# NEO-M8N_BMP280_Wing.net
KiCad netlist of a schematic drawn in EAGLE
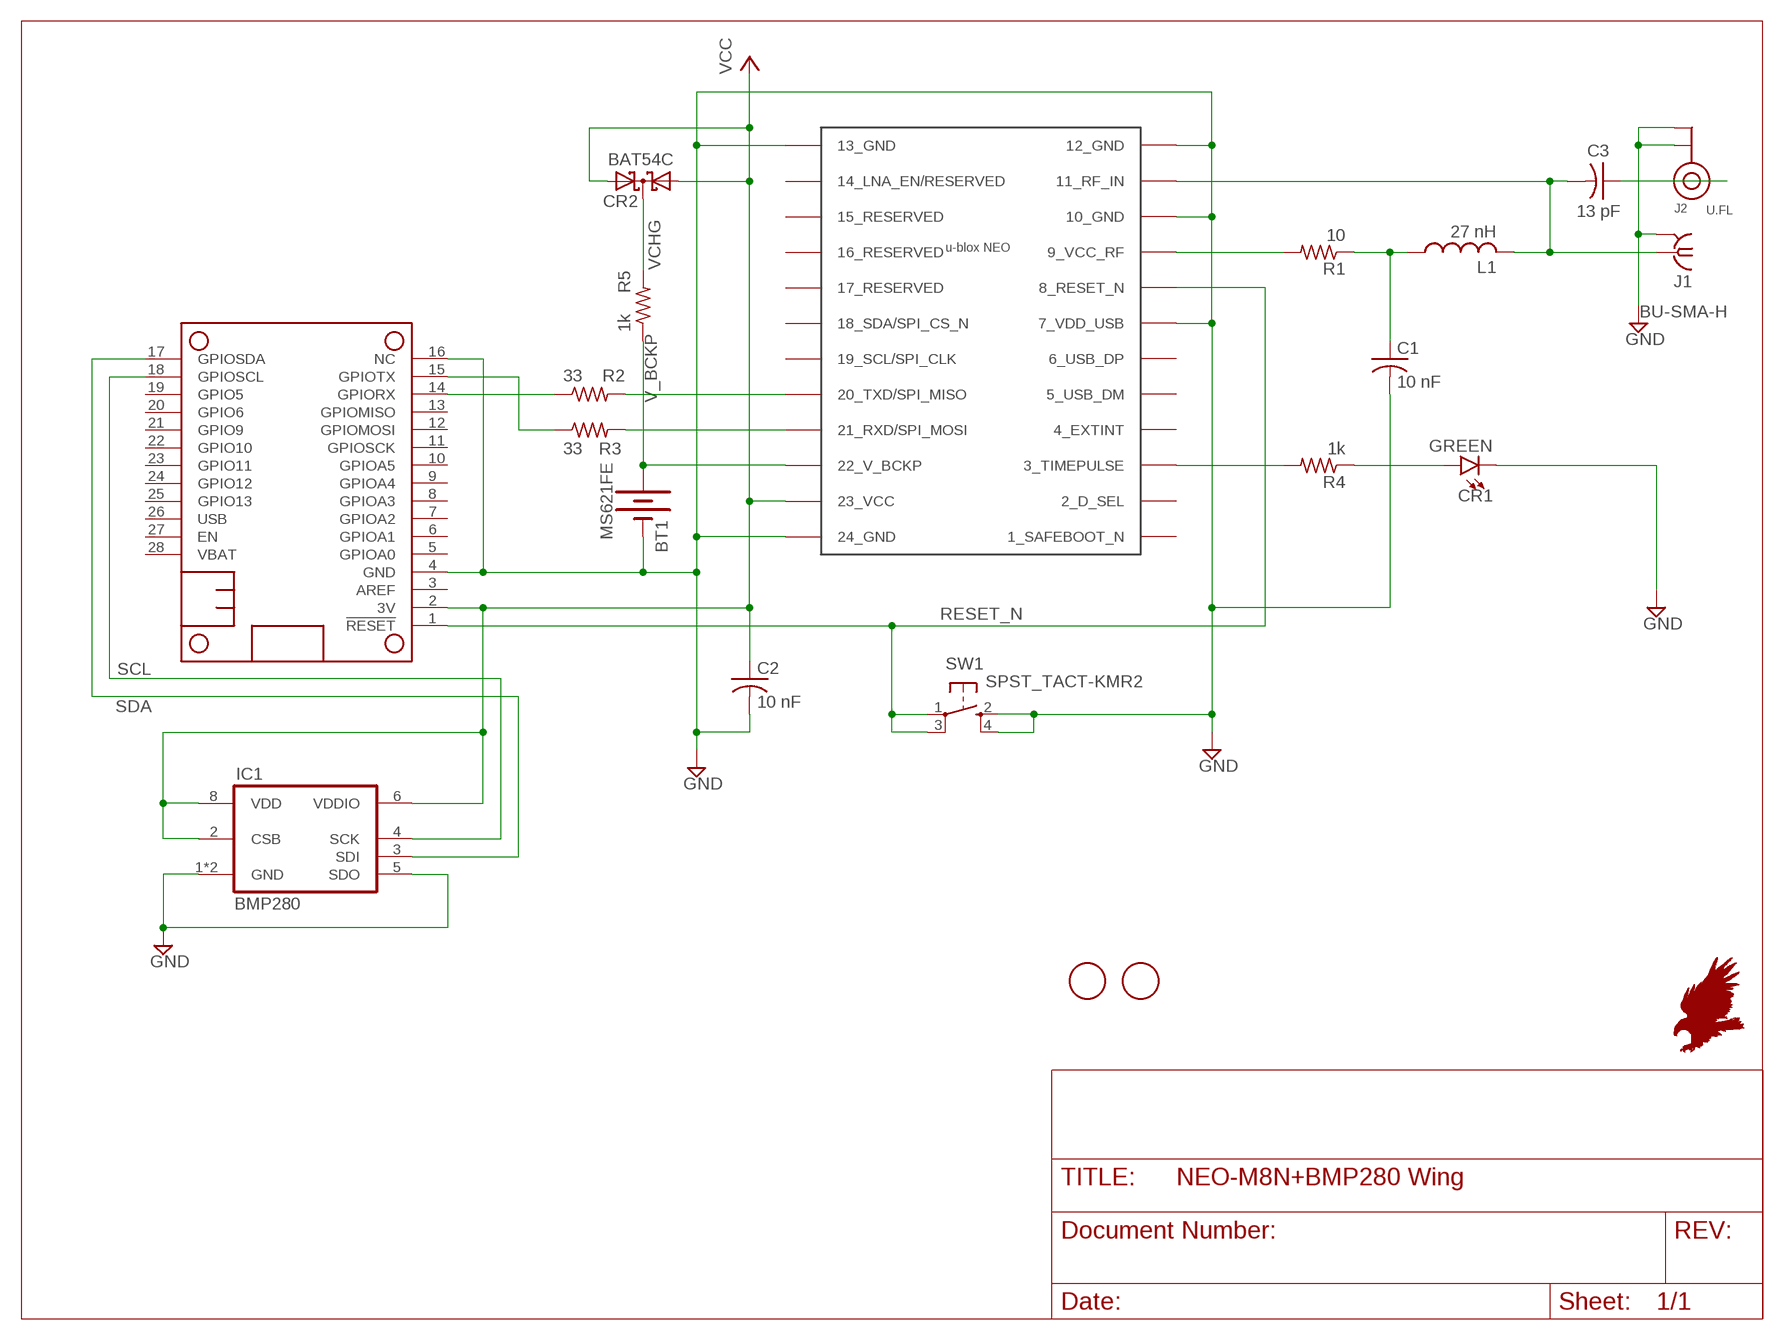
[diagram p0: schematic, sheet 1]

(export (version "E")
  (design (tool "Eeschema 10.0.6"))
  (components
    (comp (ref "BT1")
      (value "MS621FE")
      (footprint "eagle-import:BATTCON-6.8MM")
      (libsource (lib "eagle-import") (part "BATTERY-6.8MM_SMD"))
    )
    (comp (ref "C1")
      (value "10 nF")
      (footprint "eagle-import:C0402")
      (libsource (lib "eagle-import") (part "C-USC0402"))
    )
    (comp (ref "C2")
      (value "10 nF")
      (footprint "eagle-import:C0402")
      (libsource (lib "eagle-import") (part "C-USC0402"))
    )
    (comp (ref "C3")
      (value "13 pF")
      (footprint "eagle-import:C0402")
      (libsource (lib "eagle-import") (part "C-USC0402"))
    )
    (comp (ref "CR1")
      (value "GREEN")
      (footprint "eagle-import:LED-0603")
      (libsource (lib "eagle-import") (part "LED-GREEN0603"))
    )
    (comp (ref "CR2")
      (value "BAT54C")
      (footprint "eagle-import:SOT23")
      (libsource (lib "eagle-import") (part "BAT54C"))
    )
    (comp (ref "FID1")
      (value "FIDUCIAL")
      (footprint "eagle-import:FIDUCIAL_1MM")
      (libsource (lib "eagle-import") (part "FIDUCIAL"))
    )
    (comp (ref "FID2")
      (value "FIDUCIAL")
      (footprint "eagle-import:FIDUCIAL_1MM")
      (libsource (lib "eagle-import") (part "FIDUCIAL"))
    )
    (comp (ref "IC1")
      (value "BMP280")
      (footprint "eagle-import:BMP280")
      (libsource (lib "eagle-import") (part "BMP280"))
    )
    (comp (ref "J1")
      (value "BU-SMA-H")
      (footprint "eagle-import:BU-SMA-H")
      (libsource (lib "eagle-import") (part "BU-SMA-H"))
    )
    (comp (ref "J2")
      (value "U.FL")
      (footprint "eagle-import:U.FL")
      (libsource (lib "eagle-import") (part "ANTENNA_U.FL"))
    )
    (comp (ref "L1")
      (value "27 nH")
      (footprint "eagle-import:L0402")
      (libsource (lib "eagle-import") (part "L-US0402"))
    )
    (comp (ref "MS1")
      (value "FEATHERWING")
      (footprint "eagle-import:FEATHERWING")
      (libsource (lib "eagle-import") (part "FEATHERWING"))
    )
    (comp (ref "R1")
      (value "10")
      (footprint "eagle-import:R0805")
      (libsource (lib "eagle-import") (part "R-US_R0805"))
    )
    (comp (ref "R2")
      (value "33")
      (footprint "eagle-import:R0805")
      (libsource (lib "eagle-import") (part "R-US_R0805"))
    )
    (comp (ref "R3")
      (value "33")
      (footprint "eagle-import:R0805")
      (libsource (lib "eagle-import") (part "R-US_R0805"))
    )
    (comp (ref "R4")
      (value "1k")
      (footprint "eagle-import:R0805")
      (libsource (lib "eagle-import") (part "R-US_R0805"))
    )
    (comp (ref "R5")
      (value "1k")
      (footprint "eagle-import:R0805")
      (libsource (lib "eagle-import") (part "R-US_R0805"))
    )
    (comp (ref "SW1")
      (value "SPST_TACT-KMR2")
      (footprint "eagle-import:KMR2")
      (libsource (lib "eagle-import") (part "SPST_TACT-KMR2"))
    )
    (comp (ref "U$2")
      (value "NEO-M8")
      (footprint "eagle-import:NEO-M8")
      (libsource (lib "eagle-import") (part "NEO-M8"))
    )
  )
  (nets
    (net (code "1") (name "/RESET_N") (class "Default")
      (node (ref "MS1") (pin "1") (pinfunction "~{RESET}_1") (pintype "input"))
      (node (ref "SW1") (pin "1") (pinfunction "P_1") (pintype "passive"))
      (node (ref "SW1") (pin "3") (pinfunction "P1_3") (pintype "passive"))
      (node (ref "U$2") (pin "8") (pinfunction "8_RESET_N_8") (pintype "bidirectional"))
    )
    (net (code "2") (name "/SCL") (class "Default")
      (node (ref "IC1") (pin "4") (pinfunction "SCK_4") (pintype "bidirectional"))
      (node (ref "MS1") (pin "18") (pinfunction "GPIOSCL_18") (pintype "bidirectional"))
    )
    (net (code "3") (name "/SDA") (class "Default")
      (node (ref "IC1") (pin "3") (pinfunction "SDI_3") (pintype "bidirectional"))
      (node (ref "MS1") (pin "17") (pinfunction "GPIOSDA_17") (pintype "bidirectional"))
    )
    (net (code "4") (name "/USB") (class "Default")
      (node (ref "MS1") (pin "26") (pinfunction "USB_26") (pintype "power_in"))
    )
    (net (code "5") (name "/VBAT") (class "Default")
      (node (ref "MS1") (pin "28") (pinfunction "VBAT_28") (pintype "power_in"))
    )
    (net (code "6") (name "/VCHG") (class "Default")
      (node (ref "CR2") (pin "3") (pinfunction "CC_3") (pintype "passive"))
      (node (ref "R5") (pin "2") (pinfunction "2_2") (pintype "passive"))
    )
    (net (code "7") (name "/V_BCKP") (class "Default")
      (node (ref "BT1") (pin "+") (pinfunction "+_+") (pintype "power_in"))
      (node (ref "R5") (pin "1") (pinfunction "1_1") (pintype "passive"))
      (node (ref "U$2") (pin "22") (pinfunction "22_V_BCKP_22") (pintype "bidirectional"))
    )
    (net (code "8") (name "GND") (class "Default")
      (node (ref "BT1") (pin "-") (pinfunction "-_-") (pintype "power_in"))
      (node (ref "C1") (pin "2") (pinfunction "2_2") (pintype "passive"))
      (node (ref "C2") (pin "2") (pinfunction "2_2") (pintype "passive"))
      (node (ref "CR1") (pin "C") (pinfunction "C_C") (pintype "passive"))
      (node (ref "IC1") (pin "1") (pinfunction "GND_1") (pintype "power_in"))
      (node (ref "IC1") (pin "5") (pinfunction "SDO_5") (pintype "input"))
      (node (ref "IC1") (pin "7") (pinfunction "GND_7") (pintype "power_in"))
      (node (ref "J1") (pin "2") (pinfunction "2_2") (pintype "passive"))
      (node (ref "J1") (pin "3") (pinfunction "2_3") (pintype "passive"))
      (node (ref "J1") (pin "4") (pinfunction "2_4") (pintype "passive"))
      (node (ref "J1") (pin "5") (pinfunction "2_5") (pintype "passive"))
      (node (ref "J2") (pin "1") (pinfunction "GND_1") (pintype "passive"))
      (node (ref "J2") (pin "2") (pinfunction "GND_2") (pintype "passive"))
      (node (ref "MS1") (pin "16") (pinfunction "NC_16") (pintype "passive"))
      (node (ref "MS1") (pin "4") (pinfunction "GND_4") (pintype "power_in"))
      (node (ref "SW1") (pin "2") (pinfunction "S_2") (pintype "passive"))
      (node (ref "SW1") (pin "4") (pinfunction "S1_4") (pintype "passive"))
      (node (ref "U$2") (pin "10") (pinfunction "10_GND_10") (pintype "bidirectional"))
      (node (ref "U$2") (pin "12") (pinfunction "12_GND_12") (pintype "bidirectional"))
      (node (ref "U$2") (pin "13") (pinfunction "13_GND_13") (pintype "bidirectional"))
      (node (ref "U$2") (pin "24") (pinfunction "24_GND_24") (pintype "bidirectional"))
      (node (ref "U$2") (pin "7") (pinfunction "7_VDD_USB_7") (pintype "bidirectional"))
    )
    (net (code "9") (name "Net-(CR1-PadA)") (class "Default")
      (node (ref "CR1") (pin "A") (pinfunction "A_A") (pintype "passive"))
      (node (ref "R4") (pin "1") (pinfunction "1_1") (pintype "passive"))
    )
    (net (code "10") (name "Net-(J2-SIGNAL)") (class "Default")
      (node (ref "C3") (pin "1") (pinfunction "1_1") (pintype "passive"))
      (node (ref "J2") (pin "3") (pinfunction "SIGNAL_3") (pintype "passive"))
    )
    (net (code "11") (name "Net-(L1-1)") (class "Default")
      (node (ref "C1") (pin "1") (pinfunction "1_1") (pintype "passive"))
      (node (ref "L1") (pin "P$1") (pinfunction "1_P$1") (pintype "passive"))
      (node (ref "R1") (pin "1") (pinfunction "1_1") (pintype "passive"))
    )
    (net (code "12") (name "Net-(L1-2)") (class "Default")
      (node (ref "C3") (pin "2") (pinfunction "2_2") (pintype "passive"))
      (node (ref "J1") (pin "1") (pinfunction "1_1") (pintype "passive"))
      (node (ref "L1") (pin "P$2") (pinfunction "2_P$2") (pintype "passive"))
      (node (ref "U$2") (pin "11") (pinfunction "11_RF_IN_11") (pintype "bidirectional"))
    )
    (net (code "13") (name "Net-(MS1-GPIORX)") (class "Default")
      (node (ref "MS1") (pin "14") (pinfunction "GPIORX_14") (pintype "bidirectional"))
      (node (ref "R2") (pin "1") (pinfunction "1_1") (pintype "passive"))
    )
    (net (code "14") (name "Net-(MS1-GPIOTX)") (class "Default")
      (node (ref "MS1") (pin "15") (pinfunction "GPIOTX_15") (pintype "bidirectional"))
      (node (ref "R3") (pin "1") (pinfunction "1_1") (pintype "passive"))
    )
    (net (code "15") (name "Net-(U$2-3_TIMEPULSE)") (class "Default")
      (node (ref "R4") (pin "2") (pinfunction "2_2") (pintype "passive"))
      (node (ref "U$2") (pin "3") (pinfunction "3_TIMEPULSE_3") (pintype "bidirectional"))
    )
    (net (code "16") (name "Net-(U$2-9_VCC_RF)") (class "Default")
      (node (ref "R1") (pin "2") (pinfunction "2_2") (pintype "passive"))
      (node (ref "U$2") (pin "9") (pinfunction "9_VCC_RF_9") (pintype "bidirectional"))
    )
    (net (code "17") (name "Net-(U$2-20_TXD{slash}SPI_MISO)") (class "Default")
      (node (ref "R2") (pin "2") (pinfunction "2_2") (pintype "passive"))
      (node (ref "U$2") (pin "20") (pinfunction "20_TXD/SPI_MISO_20") (pintype "bidirectional"))
    )
    (net (code "18") (name "Net-(U$2-21_RXD{slash}SPI_MOSI)") (class "Default")
      (node (ref "R3") (pin "2") (pinfunction "2_2") (pintype "passive"))
      (node (ref "U$2") (pin "21") (pinfunction "21_RXD/SPI_MOSI_21") (pintype "bidirectional"))
    )
    (net (code "19") (name "VCC") (class "Default")
      (node (ref "C2") (pin "1") (pinfunction "1_1") (pintype "passive"))
      (node (ref "CR2") (pin "1") (pinfunction "A1_1") (pintype "passive"))
      (node (ref "CR2") (pin "2") (pinfunction "A2_2") (pintype "passive"))
      (node (ref "IC1") (pin "2") (pinfunction "CSB_2") (pintype "input"))
      (node (ref "IC1") (pin "6") (pinfunction "VDDIO_6") (pintype "power_in"))
      (node (ref "IC1") (pin "8") (pinfunction "VDD_8") (pintype "power_in"))
      (node (ref "MS1") (pin "2") (pinfunction "3V_2") (pintype "power_in"))
      (node (ref "U$2") (pin "23") (pinfunction "23_VCC_23") (pintype "bidirectional"))
    )
    (net (code "20") (name "unconnected-(MS1-AREF-Pad3)") (class "Default")
      (node (ref "MS1") (pin "3") (pinfunction "AREF_3") (pintype "passive"))
    )
    (net (code "21") (name "unconnected-(MS1-EN-Pad27)") (class "Default")
      (node (ref "MS1") (pin "27") (pinfunction "EN_27") (pintype "passive"))
    )
    (net (code "22") (name "unconnected-(MS1-GPIO5-Pad19)") (class "Default")
      (node (ref "MS1") (pin "19") (pinfunction "GPIO5_19") (pintype "bidirectional"))
    )
    (net (code "23") (name "unconnected-(MS1-GPIO6-Pad20)") (class "Default")
      (node (ref "MS1") (pin "20") (pinfunction "GPIO6_20") (pintype "bidirectional"))
    )
    (net (code "24") (name "unconnected-(MS1-GPIO9-Pad21)") (class "Default")
      (node (ref "MS1") (pin "21") (pinfunction "GPIO9_21") (pintype "bidirectional"))
    )
    (net (code "25") (name "unconnected-(MS1-GPIO10-Pad22)") (class "Default")
      (node (ref "MS1") (pin "22") (pinfunction "GPIO10_22") (pintype "bidirectional"))
    )
    (net (code "26") (name "unconnected-(MS1-GPIO11-Pad23)") (class "Default")
      (node (ref "MS1") (pin "23") (pinfunction "GPIO11_23") (pintype "bidirectional"))
    )
    (net (code "27") (name "unconnected-(MS1-GPIO12-Pad24)") (class "Default")
      (node (ref "MS1") (pin "24") (pinfunction "GPIO12_24") (pintype "bidirectional"))
    )
    (net (code "28") (name "unconnected-(MS1-GPIO13-Pad25)") (class "Default")
      (node (ref "MS1") (pin "25") (pinfunction "GPIO13_25") (pintype "bidirectional"))
    )
    (net (code "29") (name "unconnected-(MS1-GPIOA0-Pad5)") (class "Default")
      (node (ref "MS1") (pin "5") (pinfunction "GPIOA0_5") (pintype "bidirectional"))
    )
    (net (code "30") (name "unconnected-(MS1-GPIOA1-Pad6)") (class "Default")
      (node (ref "MS1") (pin "6") (pinfunction "GPIOA1_6") (pintype "bidirectional"))
    )
    (net (code "31") (name "unconnected-(MS1-GPIOA2-Pad7)") (class "Default")
      (node (ref "MS1") (pin "7") (pinfunction "GPIOA2_7") (pintype "bidirectional"))
    )
    (net (code "32") (name "unconnected-(MS1-GPIOA3-Pad8)") (class "Default")
      (node (ref "MS1") (pin "8") (pinfunction "GPIOA3_8") (pintype "bidirectional"))
    )
    (net (code "33") (name "unconnected-(MS1-GPIOA4-Pad9)") (class "Default")
      (node (ref "MS1") (pin "9") (pinfunction "GPIOA4_9") (pintype "bidirectional"))
    )
    (net (code "34") (name "unconnected-(MS1-GPIOA5-Pad10)") (class "Default")
      (node (ref "MS1") (pin "10") (pinfunction "GPIOA5_10") (pintype "bidirectional"))
    )
    (net (code "35") (name "unconnected-(MS1-GPIOMISO-Pad13)") (class "Default")
      (node (ref "MS1") (pin "13") (pinfunction "GPIOMISO_13") (pintype "bidirectional"))
    )
    (net (code "36") (name "unconnected-(MS1-GPIOMOSI-Pad12)") (class "Default")
      (node (ref "MS1") (pin "12") (pinfunction "GPIOMOSI_12") (pintype "bidirectional"))
    )
    (net (code "37") (name "unconnected-(MS1-GPIOSCK-Pad11)") (class "Default")
      (node (ref "MS1") (pin "11") (pinfunction "GPIOSCK_11") (pintype "bidirectional"))
    )
    (net (code "38") (name "unconnected-(U$2-1_SAFEBOOT_N-Pad1)") (class "Default")
      (node (ref "U$2") (pin "1") (pinfunction "1_SAFEBOOT_N_1") (pintype "bidirectional"))
    )
    (net (code "39") (name "unconnected-(U$2-2_D_SEL-Pad2)") (class "Default")
      (node (ref "U$2") (pin "2") (pinfunction "2_D_SEL_2") (pintype "bidirectional"))
    )
    (net (code "40") (name "unconnected-(U$2-4_EXTINT-Pad4)") (class "Default")
      (node (ref "U$2") (pin "4") (pinfunction "4_EXTINT_4") (pintype "bidirectional"))
    )
    (net (code "41") (name "unconnected-(U$2-5_USB_DM-Pad5)") (class "Default")
      (node (ref "U$2") (pin "5") (pinfunction "5_USB_DM_5") (pintype "bidirectional"))
    )
    (net (code "42") (name "unconnected-(U$2-6_USB_DP-Pad6)") (class "Default")
      (node (ref "U$2") (pin "6") (pinfunction "6_USB_DP_6") (pintype "bidirectional"))
    )
    (net (code "43") (name "unconnected-(U$2-14_LNA_EN{slash}RESERVED-Pad14)") (class "Default")
      (node (ref "U$2") (pin "14") (pinfunction "14_LNA_EN/RESERVED_14") (pintype "bidirectional"))
    )
    (net (code "44") (name "unconnected-(U$2-15_RESERVED-Pad15)") (class "Default")
      (node (ref "U$2") (pin "15") (pinfunction "15_RESERVED_15") (pintype "bidirectional"))
    )
    (net (code "45") (name "unconnected-(U$2-16_RESERVED-Pad16)") (class "Default")
      (node (ref "U$2") (pin "16") (pinfunction "16_RESERVED_16") (pintype "bidirectional"))
    )
    (net (code "46") (name "unconnected-(U$2-17_RESERVED-Pad17)") (class "Default")
      (node (ref "U$2") (pin "17") (pinfunction "17_RESERVED_17") (pintype "bidirectional"))
    )
    (net (code "47") (name "unconnected-(U$2-18_SDA{slash}SPI_CS_N-Pad18)") (class "Default")
      (node (ref "U$2") (pin "18") (pinfunction "18_SDA/SPI_CS_N_18") (pintype "bidirectional"))
    )
    (net (code "48") (name "unconnected-(U$2-19_SCL{slash}SPI_CLK-Pad19)") (class "Default")
      (node (ref "U$2") (pin "19") (pinfunction "19_SCL/SPI_CLK_19") (pintype "bidirectional"))
    )
  )
)
